# BreakoutTRRS.net
KiCad netlist of a schematic drawn in EAGLE
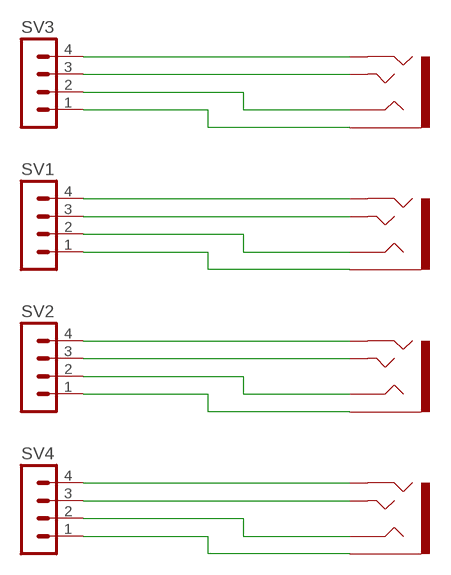
[diagram p0: schematic, sheet 1]

(export (version "E")
  (design (tool "Eeschema 10.0.6"))
  (components
    (comp (ref "SV1")
      (value "MA04-1")
      (footprint "eagle-import:MA04-1")
      (libsource (lib "eagle-import") (part "MA04-1"))
    )
    (comp (ref "SV2")
      (value "MA04-1")
      (footprint "eagle-import:MA04-1")
      (libsource (lib "eagle-import") (part "MA04-1"))
    )
    (comp (ref "SV3")
      (value "MA04-1")
      (footprint "eagle-import:MA04-1")
      (libsource (lib "eagle-import") (part "MA04-1"))
    )
    (comp (ref "SV4")
      (value "MA04-1")
      (footprint "eagle-import:MA04-1")
      (libsource (lib "eagle-import") (part "MA04-1"))
    )
    (comp (ref "TO-HEADSET1")
      (value "AUDIO-JACK3")
      (footprint "eagle-import:AUDIO-JACK-TRRS-SMD")
      (libsource (lib "eagle-import") (part "AUDIO-JACK3"))
    )
    (comp (ref "TO-HEADSET2")
      (value "AUDIO-JACK3")
      (footprint "eagle-import:AUDIO-JACK-TRRS-SMD")
      (libsource (lib "eagle-import") (part "AUDIO-JACK3"))
    )
    (comp (ref "TO-HEADSET3")
      (value "AUDIO-JACK3")
      (footprint "eagle-import:AUDIO-JACK-TRRS-SMD")
      (libsource (lib "eagle-import") (part "AUDIO-JACK3"))
    )
    (comp (ref "TO-HEADSET4")
      (value "AUDIO-JACK3")
      (footprint "eagle-import:AUDIO-JACK-TRRS-SMD")
      (libsource (lib "eagle-import") (part "AUDIO-JACK3"))
    )
  )
  (nets
    (net (code "1") (name "Net-(SV1-Pad1)") (class "Default")
      (node (ref "SV1") (pin "1") (pinfunction "1_1") (pintype "passive"))
      (node (ref "TO-HEADSET2") (pin "EARTH") (pinfunction "EARTH_EARTH") (pintype "bidirectional"))
    )
    (net (code "2") (name "Net-(SV1-Pad2)") (class "Default")
      (node (ref "SV1") (pin "2") (pinfunction "2_2") (pintype "passive"))
      (node (ref "TO-HEADSET2") (pin "RING1") (pinfunction "RING1_RING1") (pintype "bidirectional"))
    )
    (net (code "3") (name "Net-(SV1-Pad3)") (class "Default")
      (node (ref "SV1") (pin "3") (pinfunction "3_3") (pintype "passive"))
      (node (ref "TO-HEADSET2") (pin "TIP") (pinfunction "TIP_TIP") (pintype "bidirectional"))
    )
    (net (code "4") (name "Net-(SV1-Pad4)") (class "Default")
      (node (ref "SV1") (pin "4") (pinfunction "4_4") (pintype "passive"))
      (node (ref "TO-HEADSET2") (pin "RING2") (pinfunction "RING2_RING2") (pintype "bidirectional"))
    )
    (net (code "5") (name "Net-(SV2-Pad1)") (class "Default")
      (node (ref "SV2") (pin "1") (pinfunction "1_1") (pintype "passive"))
      (node (ref "TO-HEADSET1") (pin "EARTH") (pinfunction "EARTH_EARTH") (pintype "bidirectional"))
    )
    (net (code "6") (name "Net-(SV2-Pad2)") (class "Default")
      (node (ref "SV2") (pin "2") (pinfunction "2_2") (pintype "passive"))
      (node (ref "TO-HEADSET1") (pin "RING1") (pinfunction "RING1_RING1") (pintype "bidirectional"))
    )
    (net (code "7") (name "Net-(SV2-Pad3)") (class "Default")
      (node (ref "SV2") (pin "3") (pinfunction "3_3") (pintype "passive"))
      (node (ref "TO-HEADSET1") (pin "TIP") (pinfunction "TIP_TIP") (pintype "bidirectional"))
    )
    (net (code "8") (name "Net-(SV2-Pad4)") (class "Default")
      (node (ref "SV2") (pin "4") (pinfunction "4_4") (pintype "passive"))
      (node (ref "TO-HEADSET1") (pin "RING2") (pinfunction "RING2_RING2") (pintype "bidirectional"))
    )
    (net (code "9") (name "Net-(SV3-Pad1)") (class "Default")
      (node (ref "SV3") (pin "1") (pinfunction "1_1") (pintype "passive"))
      (node (ref "TO-HEADSET3") (pin "EARTH") (pinfunction "EARTH_EARTH") (pintype "bidirectional"))
    )
    (net (code "10") (name "Net-(SV3-Pad2)") (class "Default")
      (node (ref "SV3") (pin "2") (pinfunction "2_2") (pintype "passive"))
      (node (ref "TO-HEADSET3") (pin "RING1") (pinfunction "RING1_RING1") (pintype "bidirectional"))
    )
    (net (code "11") (name "Net-(SV3-Pad3)") (class "Default")
      (node (ref "SV3") (pin "3") (pinfunction "3_3") (pintype "passive"))
      (node (ref "TO-HEADSET3") (pin "TIP") (pinfunction "TIP_TIP") (pintype "bidirectional"))
    )
    (net (code "12") (name "Net-(SV3-Pad4)") (class "Default")
      (node (ref "SV3") (pin "4") (pinfunction "4_4") (pintype "passive"))
      (node (ref "TO-HEADSET3") (pin "RING2") (pinfunction "RING2_RING2") (pintype "bidirectional"))
    )
    (net (code "13") (name "Net-(SV4-Pad1)") (class "Default")
      (node (ref "SV4") (pin "1") (pinfunction "1_1") (pintype "passive"))
      (node (ref "TO-HEADSET4") (pin "EARTH") (pinfunction "EARTH_EARTH") (pintype "bidirectional"))
    )
    (net (code "14") (name "Net-(SV4-Pad2)") (class "Default")
      (node (ref "SV4") (pin "2") (pinfunction "2_2") (pintype "passive"))
      (node (ref "TO-HEADSET4") (pin "RING1") (pinfunction "RING1_RING1") (pintype "bidirectional"))
    )
    (net (code "15") (name "Net-(SV4-Pad3)") (class "Default")
      (node (ref "SV4") (pin "3") (pinfunction "3_3") (pintype "passive"))
      (node (ref "TO-HEADSET4") (pin "TIP") (pinfunction "TIP_TIP") (pintype "bidirectional"))
    )
    (net (code "16") (name "Net-(SV4-Pad4)") (class "Default")
      (node (ref "SV4") (pin "4") (pinfunction "4_4") (pintype "passive"))
      (node (ref "TO-HEADSET4") (pin "RING2") (pinfunction "RING2_RING2") (pintype "bidirectional"))
    )
  )
)
